# Red_Buggy_2015.net
KiCad netlist of a schematic drawn in EAGLE
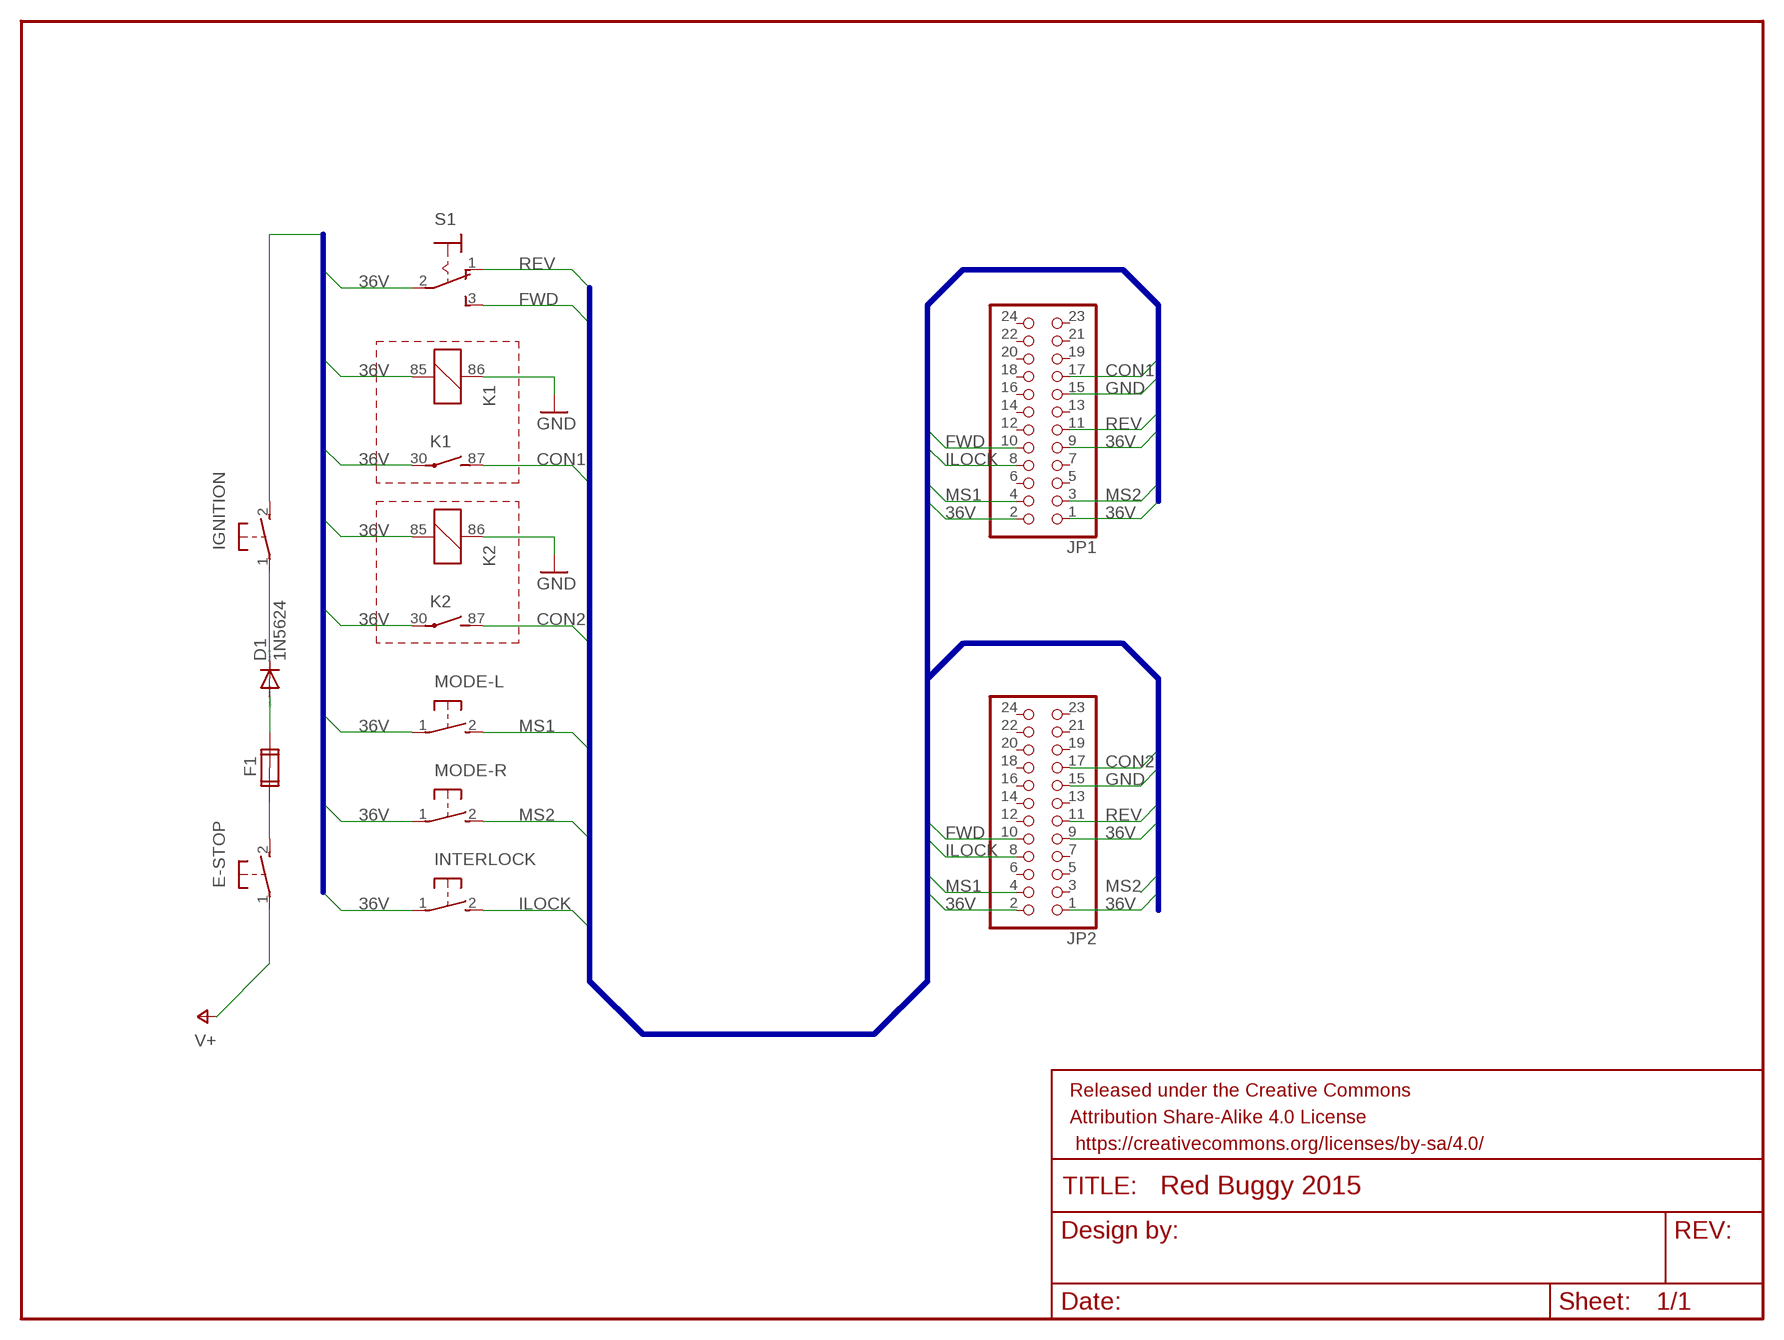
[diagram p0: schematic, sheet 1]

(export (version "E")
  (design (tool "Eeschema 10.0.6"))
  (components
    (comp (ref "D1")
      (value "1N5624")
      (footprint "eagle-import:DO201-15")
      (libsource (lib "eagle-import") (part "1N5624"))
    )
    (comp (ref "E-STOP")
      (value "31-XX")
      (footprint "eagle-import:B3F-31XX")
      (libsource (lib "eagle-import") (part "31-XX"))
    )
    (comp (ref "F1")
      (value "FUSE2P")
      (footprint "eagle-import:FUSE1")
      (libsource (lib "eagle-import") (part "FUSE2P"))
    )
    (comp (ref "FRAME1")
      (value "FRAME-LETTER")
      (footprint "eagle-import:CREATIVE_COMMONS")
      (libsource (lib "eagle-import") (part "FRAME-LETTER"))
    )
    (comp (ref "IGNITION")
      (value "31-XX")
      (footprint "eagle-import:B3F-31XX")
      (libsource (lib "eagle-import") (part "31-XX"))
    )
    (comp (ref "INTERLOCK")
      (value "31-XX")
      (footprint "eagle-import:B3F-31XX")
      (libsource (lib "eagle-import") (part "31-XX"))
    )
    (comp (ref "JP1")
      (value "PINHD-2X12")
      (footprint "eagle-import:2X12")
      (libsource (lib "eagle-import") (part "PINHD-2X12"))
    )
    (comp (ref "JP2")
      (value "PINHD-2X12")
      (footprint "eagle-import:2X12")
      (libsource (lib "eagle-import") (part "PINHD-2X12"))
    )
    (comp (ref "K1")
      (value "CB1A-P-12V")
      (footprint "eagle-import:CB1")
      (fields (field (name "MF") "AROMAT/ MATSUSHITA"))
      (libsource (lib "eagle-import") (part "CB1A-P-12V"))
    )
    (comp (ref "K2")
      (value "CB1A-P-12V")
      (footprint "eagle-import:CB1")
      (fields (field (name "MF") "AROMAT/ MATSUSHITA"))
      (libsource (lib "eagle-import") (part "CB1A-P-12V"))
    )
    (comp (ref "MODE-L")
      (value "31-XX")
      (footprint "eagle-import:B3F-31XX")
      (libsource (lib "eagle-import") (part "31-XX"))
    )
    (comp (ref "MODE-R")
      (value "31-XX")
      (footprint "eagle-import:B3F-31XX")
      (libsource (lib "eagle-import") (part "31-XX"))
    )
    (comp (ref "S1")
      (value "320-916")
      (footprint "eagle-import:320-916")
      (libsource (lib "eagle-import") (part "320-916"))
    )
  )
  (nets
    (net (code "1") (name "/36V") (class "Default")
      (node (ref "IGNITION") (pin "2") (pinfunction "S_2") (pintype "passive"))
      (node (ref "INTERLOCK") (pin "1") (pinfunction "P_1") (pintype "passive"))
      (node (ref "JP1") (pin "1") (pinfunction "1_1") (pintype "passive"))
      (node (ref "JP1") (pin "2") (pinfunction "2_2") (pintype "passive"))
      (node (ref "JP1") (pin "9") (pinfunction "9_9") (pintype "passive"))
      (node (ref "JP2") (pin "1") (pinfunction "1_1") (pintype "passive"))
      (node (ref "JP2") (pin "2") (pinfunction "2_2") (pintype "passive"))
      (node (ref "JP2") (pin "9") (pinfunction "9_9") (pintype "passive"))
      (node (ref "K1") (pin "30") (pinfunction "P_30") (pintype "passive"))
      (node (ref "K1") (pin "85") (pinfunction "2_85") (pintype "passive"))
      (node (ref "K2") (pin "30") (pinfunction "P_30") (pintype "passive"))
      (node (ref "K2") (pin "85") (pinfunction "2_85") (pintype "passive"))
      (node (ref "MODE-L") (pin "1") (pinfunction "P_1") (pintype "passive"))
      (node (ref "MODE-R") (pin "1") (pinfunction "P_1") (pintype "passive"))
      (node (ref "S1") (pin "2") (pinfunction "P_2") (pintype "passive"))
    )
    (net (code "2") (name "/CON1") (class "Default")
      (node (ref "JP1") (pin "17") (pinfunction "17_17") (pintype "passive"))
      (node (ref "K1") (pin "87") (pinfunction "S_87") (pintype "passive"))
    )
    (net (code "3") (name "/CON2") (class "Default")
      (node (ref "JP2") (pin "17") (pinfunction "17_17") (pintype "passive"))
      (node (ref "K2") (pin "87") (pinfunction "S_87") (pintype "passive"))
    )
    (net (code "4") (name "/FWD") (class "Default")
      (node (ref "JP1") (pin "10") (pinfunction "10_10") (pintype "passive"))
      (node (ref "JP2") (pin "10") (pinfunction "10_10") (pintype "passive"))
      (node (ref "S1") (pin "3") (pinfunction "S_3") (pintype "passive"))
    )
    (net (code "5") (name "/ILOCK") (class "Default")
      (node (ref "INTERLOCK") (pin "2") (pinfunction "S_2") (pintype "passive"))
      (node (ref "JP1") (pin "8") (pinfunction "8_8") (pintype "passive"))
      (node (ref "JP2") (pin "8") (pinfunction "8_8") (pintype "passive"))
    )
    (net (code "6") (name "/MS1") (class "Default")
      (node (ref "JP1") (pin "4") (pinfunction "4_4") (pintype "passive"))
      (node (ref "JP2") (pin "4") (pinfunction "4_4") (pintype "passive"))
      (node (ref "MODE-L") (pin "2") (pinfunction "S_2") (pintype "passive"))
    )
    (net (code "7") (name "/MS2") (class "Default")
      (node (ref "JP1") (pin "3") (pinfunction "3_3") (pintype "passive"))
      (node (ref "MODE-R") (pin "2") (pinfunction "S_2") (pintype "passive"))
    )
    (net (code "8") (name "/REV") (class "Default")
      (node (ref "JP1") (pin "11") (pinfunction "11_11") (pintype "passive"))
      (node (ref "JP2") (pin "11") (pinfunction "11_11") (pintype "passive"))
      (node (ref "S1") (pin "1") (pinfunction "O_1") (pintype "passive"))
    )
    (net (code "9") (name "GND") (class "Default")
      (node (ref "JP1") (pin "15") (pinfunction "15_15") (pintype "passive"))
      (node (ref "JP2") (pin "15") (pinfunction "15_15") (pintype "passive"))
      (node (ref "K1") (pin "86") (pinfunction "1_86") (pintype "passive"))
      (node (ref "K2") (pin "86") (pinfunction "1_86") (pintype "passive"))
    )
    (net (code "10") (name "Net-(D1-PadA)") (class "Default")
      (node (ref "D1") (pin "A") (pinfunction "A_A") (pintype "passive"))
      (node (ref "F1") (pin "2A") (pinfunction "2A_2A") (pintype "passive"))
    )
    (net (code "11") (name "Net-(E-STOP-S)") (class "Default")
      (node (ref "E-STOP") (pin "2") (pinfunction "S_2") (pintype "passive"))
      (node (ref "F1") (pin "1A") (pinfunction "1A_1A") (pintype "passive"))
    )
    (net (code "12") (name "Net-(IGNITION-P)") (class "Default")
      (node (ref "D1") (pin "C") (pinfunction "C_C") (pintype "passive"))
      (node (ref "IGNITION") (pin "1") (pinfunction "P_1") (pintype "passive"))
    )
    (net (code "13") (name "V+") (class "Default")
      (node (ref "E-STOP") (pin "1") (pinfunction "P_1") (pintype "passive"))
    )
    (net (code "14") (name "unconnected-(F1-Pad1B)") (class "Default")
      (node (ref "F1") (pin "1B") (pinfunction "1B_1B") (pintype "passive"))
    )
    (net (code "15") (name "unconnected-(F1-Pad2B)") (class "Default")
      (node (ref "F1") (pin "2B") (pinfunction "2B_2B") (pintype "passive"))
    )
    (net (code "16") (name "unconnected-(JP1-Pad5)") (class "Default")
      (node (ref "JP1") (pin "5") (pinfunction "5_5") (pintype "passive"))
    )
    (net (code "17") (name "unconnected-(JP1-Pad6)") (class "Default")
      (node (ref "JP1") (pin "6") (pinfunction "6_6") (pintype "passive"))
    )
    (net (code "18") (name "unconnected-(JP1-Pad7)") (class "Default")
      (node (ref "JP1") (pin "7") (pinfunction "7_7") (pintype "passive"))
    )
    (net (code "19") (name "unconnected-(JP1-Pad12)") (class "Default")
      (node (ref "JP1") (pin "12") (pinfunction "12_12") (pintype "passive"))
    )
    (net (code "20") (name "unconnected-(JP1-Pad13)") (class "Default")
      (node (ref "JP1") (pin "13") (pinfunction "13_13") (pintype "passive"))
    )
    (net (code "21") (name "unconnected-(JP1-Pad14)") (class "Default")
      (node (ref "JP1") (pin "14") (pinfunction "14_14") (pintype "passive"))
    )
    (net (code "22") (name "unconnected-(JP1-Pad16)") (class "Default")
      (node (ref "JP1") (pin "16") (pinfunction "16_16") (pintype "passive"))
    )
    (net (code "23") (name "unconnected-(JP1-Pad18)") (class "Default")
      (node (ref "JP1") (pin "18") (pinfunction "18_18") (pintype "passive"))
    )
    (net (code "24") (name "unconnected-(JP1-Pad19)") (class "Default")
      (node (ref "JP1") (pin "19") (pinfunction "19_19") (pintype "passive"))
    )
    (net (code "25") (name "unconnected-(JP1-Pad20)") (class "Default")
      (node (ref "JP1") (pin "20") (pinfunction "20_20") (pintype "passive"))
    )
    (net (code "26") (name "unconnected-(JP1-Pad21)") (class "Default")
      (node (ref "JP1") (pin "21") (pinfunction "21_21") (pintype "passive"))
    )
    (net (code "27") (name "unconnected-(JP1-Pad22)") (class "Default")
      (node (ref "JP1") (pin "22") (pinfunction "22_22") (pintype "passive"))
    )
    (net (code "28") (name "unconnected-(JP1-Pad23)") (class "Default")
      (node (ref "JP1") (pin "23") (pinfunction "23_23") (pintype "passive"))
    )
    (net (code "29") (name "unconnected-(JP1-Pad24)") (class "Default")
      (node (ref "JP1") (pin "24") (pinfunction "24_24") (pintype "passive"))
    )
    (net (code "30") (name "unconnected-(JP2-Pad3)") (class "Default")
      (node (ref "JP2") (pin "3") (pinfunction "3_3") (pintype "passive"))
    )
    (net (code "31") (name "unconnected-(JP2-Pad5)") (class "Default")
      (node (ref "JP2") (pin "5") (pinfunction "5_5") (pintype "passive"))
    )
    (net (code "32") (name "unconnected-(JP2-Pad6)") (class "Default")
      (node (ref "JP2") (pin "6") (pinfunction "6_6") (pintype "passive"))
    )
    (net (code "33") (name "unconnected-(JP2-Pad7)") (class "Default")
      (node (ref "JP2") (pin "7") (pinfunction "7_7") (pintype "passive"))
    )
    (net (code "34") (name "unconnected-(JP2-Pad12)") (class "Default")
      (node (ref "JP2") (pin "12") (pinfunction "12_12") (pintype "passive"))
    )
    (net (code "35") (name "unconnected-(JP2-Pad13)") (class "Default")
      (node (ref "JP2") (pin "13") (pinfunction "13_13") (pintype "passive"))
    )
    (net (code "36") (name "unconnected-(JP2-Pad14)") (class "Default")
      (node (ref "JP2") (pin "14") (pinfunction "14_14") (pintype "passive"))
    )
    (net (code "37") (name "unconnected-(JP2-Pad16)") (class "Default")
      (node (ref "JP2") (pin "16") (pinfunction "16_16") (pintype "passive"))
    )
    (net (code "38") (name "unconnected-(JP2-Pad18)") (class "Default")
      (node (ref "JP2") (pin "18") (pinfunction "18_18") (pintype "passive"))
    )
    (net (code "39") (name "unconnected-(JP2-Pad19)") (class "Default")
      (node (ref "JP2") (pin "19") (pinfunction "19_19") (pintype "passive"))
    )
    (net (code "40") (name "unconnected-(JP2-Pad20)") (class "Default")
      (node (ref "JP2") (pin "20") (pinfunction "20_20") (pintype "passive"))
    )
    (net (code "41") (name "unconnected-(JP2-Pad21)") (class "Default")
      (node (ref "JP2") (pin "21") (pinfunction "21_21") (pintype "passive"))
    )
    (net (code "42") (name "unconnected-(JP2-Pad22)") (class "Default")
      (node (ref "JP2") (pin "22") (pinfunction "22_22") (pintype "passive"))
    )
    (net (code "43") (name "unconnected-(JP2-Pad23)") (class "Default")
      (node (ref "JP2") (pin "23") (pinfunction "23_23") (pintype "passive"))
    )
    (net (code "44") (name "unconnected-(JP2-Pad24)") (class "Default")
      (node (ref "JP2") (pin "24") (pinfunction "24_24") (pintype "passive"))
    )
  )
)
